# POWER.net
KiCad netlist of a schematic drawn in Altium Designer
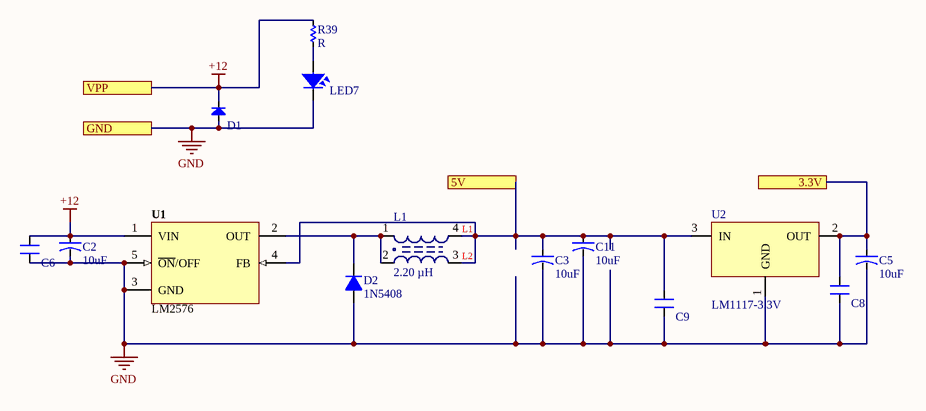
[diagram p0: POWER.SchDoc]

(export (version "E")
  (design (tool "Eeschema 10.0.6"))
  (components
    (comp (ref "C2")
      (value "10uF")
      (footprint "CAP-ALU-SMD-6.3x7.7x2.2")
      (description "Polarized Capacitor (Axial)")
      (fields (field (name "PUBLISHER") "Altium Limited"))
      (libsource (lib "LIBRARY") (part "CN-ALU-SMD"))
    )
    (comp (ref "C3")
      (value "10uF")
      (footprint "CAP-ALU-SMD-6.3x7.7x2.2")
      (description "Polarized Capacitor (Axial)")
      (fields (field (name "PUBLISHER") "Altium Limited"))
      (libsource (lib "LIBRARY") (part "CN-ALU-SMD"))
    )
    (comp (ref "C5")
      (value "10uF")
      (footprint "CAP-ALU-SMD-6.3x7.7x2.2")
      (description "Polarized Capacitor (Axial)")
      (fields (field (name "PUBLISHER") "Altium Limited"))
      (libsource (lib "LIBRARY") (part "CN-ALU-SMD"))
    )
    (comp (ref "C6") (value "CN") (footprint "CN-SMD-0603_big") (libsource (lib "nhan") (part "CN")))
    (comp (ref "C8") (value "CN") (footprint "CN-SMD-0603_big") (libsource (lib "nhan") (part "CN")))
    (comp (ref "C9") (value "CN") (footprint "CN-SMD-0603_big") (libsource (lib "nhan") (part "CN")))
    (comp (ref "C11")
      (value "10uF")
      (footprint "CAP-ALU-SMD-6.3x7.7x2.2")
      (description "Polarized Capacitor (Axial)")
      (fields (field (name "PUBLISHER") "Altium Limited"))
      (libsource (lib "LIBRARY") (part "CN-ALU-SMD"))
    )
    (comp (ref "D1")
      (value "Diode")
      (footprint "DIO-SMD-214AC")
      (description "Default Diode")
      (fields (field (name "PUBLISHER") "Altium Limited"))
      (libsource (lib "nhan") (part "Diode"))
    )
    (comp (ref "D2")
      (value "1N5408")
      (footprint "D5AN")
      (description "Diode 5A")
      (libsource (lib "syhaunguyen") (part "D5A"))
    )
    (comp (ref "L1")
      (value "2.20 µH")
      (footprint "L-SMD-D-12.5x12.5")
      (fields
        (field (name "PARTNO") "7448709022")
        (field (name "MANUFACTURER") "Würth Elektronik eiSos GmbH")
        (field (name "CREATED BY") "Christin Otto")
      )
      (libsource (lib "LIBRARY") (part "L-SMD-2"))
    )
    (comp (ref "LED7") (value "LED") (footprint "LED-0805-Blue") (libsource (lib "LIBRARY") (part "LED SMD")))
    (comp (ref "R39") (value "R") (footprint "RES-SMD-0603_BIG") (libsource (lib "nhan") (part "R")))
    (comp (ref "U1") (value "LM2576") (footprint "TO263") (libsource (lib "LIBRARY") (part "LM2576")))
    (comp (ref "U2")
      (value "LM1117-3.3V")
      (footprint "SOT223")
      (description "800mA Low-Dropout Linear Regulator")
      (fields (field (name "CREATOR") "Nguyen Ba Bien"))
      (libsource (lib "LIBRARY") (part "LM1117"))
    )
  )
  (nets
    (net (code "1") (name "+12") (class "Default")
      (node (ref "C2") (pin "1") (pinfunction "1_1") (pintype "passive"))
      (node (ref "C6") (pin "2") (pinfunction "2_2") (pintype "passive"))
      (node (ref "D1") (pin "2") (pinfunction "K_2") (pintype "passive"))
      (node (ref "R39") (pin "1") (pinfunction "1_1") (pintype "passive"))
      (node (ref "U1") (pin "1") (pinfunction "VIN_1") (pintype "power_in"))
    )
    (net (code "2") (name "/3.3V") (class "Default")
      (node (ref "C5") (pin "1") (pinfunction "1_1") (pintype "passive"))
      (node (ref "C8") (pin "2") (pinfunction "2_2") (pintype "passive"))
      (node (ref "U2") (pin "2") (pinfunction "OUT_2") (pintype "passive"))
    )
    (net (code "3") (name "/5V") (class "Default")
      (node (ref "C11") (pin "1") (pinfunction "1_1") (pintype "passive"))
      (node (ref "C3") (pin "1") (pinfunction "1_1") (pintype "passive"))
      (node (ref "C9") (pin "2") (pinfunction "2_2") (pintype "passive"))
      (node (ref "L1") (pin "3") (pinfunction "3_3") (pintype "passive"))
      (node (ref "L1") (pin "4") (pinfunction "4_4") (pintype "passive"))
      (node (ref "U1") (pin "4") (pinfunction "FB_4") (pintype "input"))
      (node (ref "U2") (pin "3") (pinfunction "IN_3") (pintype "passive"))
    )
    (net (code "4") (name "GND") (class "Default")
      (node (ref "C11") (pin "2") (pinfunction "2_2") (pintype "passive"))
      (node (ref "C2") (pin "2") (pinfunction "2_2") (pintype "passive"))
      (node (ref "C3") (pin "2") (pinfunction "2_2") (pintype "passive"))
      (node (ref "C5") (pin "2") (pinfunction "2_2") (pintype "passive"))
      (node (ref "C6") (pin "1") (pinfunction "1_1") (pintype "passive"))
      (node (ref "C8") (pin "1") (pinfunction "1_1") (pintype "passive"))
      (node (ref "C9") (pin "1") (pinfunction "1_1") (pintype "passive"))
      (node (ref "D1") (pin "1") (pinfunction "A_1") (pintype "passive"))
      (node (ref "D2") (pin "1") (pinfunction "A_1") (pintype "passive"))
      (node (ref "LED7") (pin "2") (pinfunction "2_2") (pintype "passive"))
      (node (ref "U1") (pin "3") (pinfunction "GND_3") (pintype "power_in"))
      (node (ref "U1") (pin "5") (pinfunction "~{ON}/OFF_5") (pintype "input"))
      (node (ref "U2") (pin "1") (pinfunction "GND_1") (pintype "passive"))
    )
    (net (code "5") (name "Net-(D2-K)") (class "Default")
      (node (ref "D2") (pin "2") (pinfunction "K_2") (pintype "passive"))
      (node (ref "L1") (pin "1") (pinfunction "1_1") (pintype "passive"))
      (node (ref "L1") (pin "2") (pinfunction "2_2") (pintype "passive"))
      (node (ref "U1") (pin "2") (pinfunction "OUT_2") (pintype "power_in"))
    )
    (net (code "6") (name "Net-(LED7-Pad1)") (class "Default")
      (node (ref "LED7") (pin "1") (pinfunction "1_1") (pintype "passive"))
      (node (ref "R39") (pin "2") (pinfunction "2_2") (pintype "passive"))
    )
  )
)
